# Sheet1.net
KiCad netlist of a schematic drawn in Altium Designer
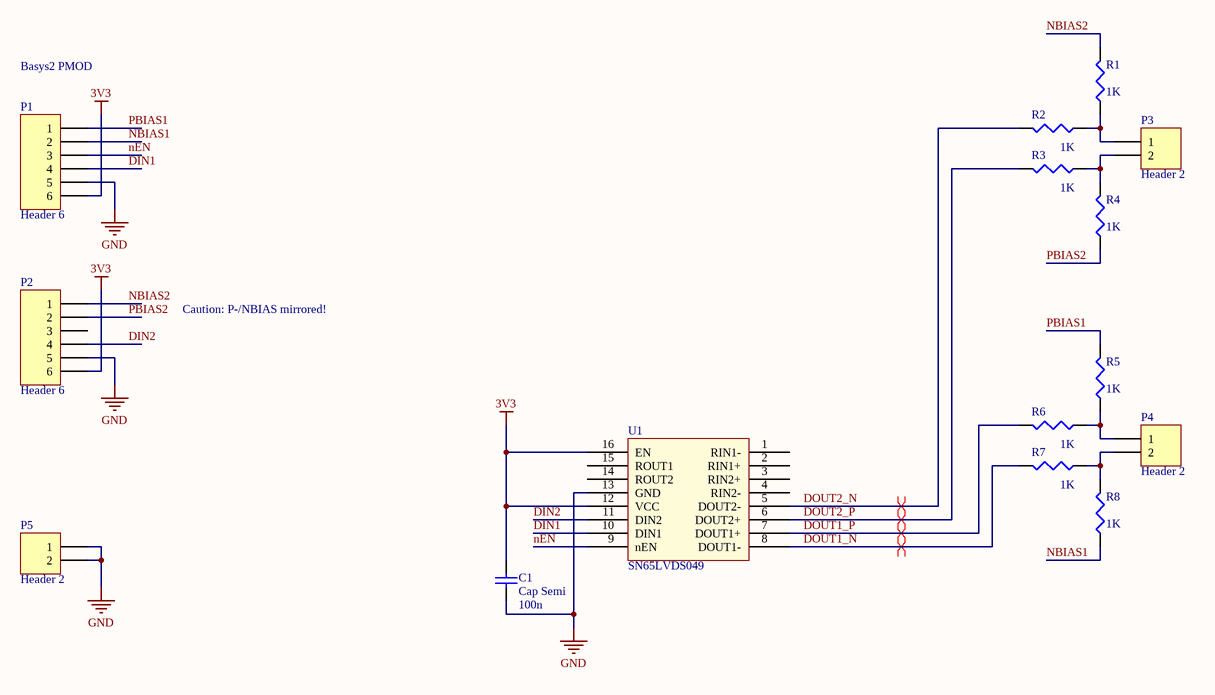
[diagram p0: Sheet1.SchDoc]

(export (version "E")
  (design (tool "Eeschema 10.0.6"))
  (components
    (comp (ref "C1")
      (value "Cap Semi")
      (footprint "1608[0603]")
      (description "Capacitor (Semiconductor SIM Model)")
      (fields (field (name "ALTIUM_VALUE") "100n") (field (name "PUBLISHER") "Altium Limited"))
      (libsource (lib "Miscellaneous Devices") (part "Cap Semi"))
    )
    (comp (ref "P1")
      (value "Header 6")
      (footprint "HDR1X6")
      (description "Header, 6-Pin")
      (fields (field (name "PUBLISHER") "Altium Limited"))
      (libsource (lib "Miscellaneous Connectors") (part "Header 6"))
    )
    (comp (ref "P2")
      (value "Header 6")
      (footprint "HDR1X6")
      (description "Header, 6-Pin")
      (fields (field (name "PUBLISHER") "Altium Limited"))
      (libsource (lib "Miscellaneous Connectors") (part "Header 6"))
    )
    (comp (ref "P3")
      (value "Header 2")
      (footprint "HDR1X2")
      (description "Header, 2-Pin")
      (fields (field (name "PUBLISHER") "Altium Limited"))
      (libsource (lib "Miscellaneous Connectors") (part "Header 2"))
    )
    (comp (ref "P4")
      (value "Header 2")
      (footprint "HDR1X2")
      (description "Header, 2-Pin")
      (fields (field (name "PUBLISHER") "Altium Limited"))
      (libsource (lib "Miscellaneous Connectors") (part "Header 2"))
    )
    (comp (ref "P5")
      (value "Header 2")
      (footprint "HDR1X2")
      (description "Header, 2-Pin")
      (fields (field (name "PUBLISHER") "Altium Limited"))
      (libsource (lib "") (part "Header 2_1"))
    )
    (comp (ref "R1")
      (value "1K")
      (footprint "J1-0603")
      (description "Resistor")
      (fields (field (name "Comment") "Res3") (field (name "PUBLISHER") "Altium Limited"))
      (libsource (lib "Miscellaneous Devices") (part "Res3"))
    )
    (comp (ref "R2")
      (value "1K")
      (footprint "J1-0603")
      (description "Resistor")
      (fields (field (name "Comment") "Res3") (field (name "PUBLISHER") "Altium Limited"))
      (libsource (lib "Miscellaneous Devices") (part "Res3"))
    )
    (comp (ref "R3")
      (value "1K")
      (footprint "J1-0603")
      (description "Resistor")
      (fields (field (name "Comment") "Res3") (field (name "PUBLISHER") "Altium Limited"))
      (libsource (lib "Miscellaneous Devices") (part "Res3"))
    )
    (comp (ref "R4")
      (value "1K")
      (footprint "J1-0603")
      (description "Resistor")
      (fields (field (name "Comment") "Res3") (field (name "PUBLISHER") "Altium Limited"))
      (libsource (lib "Miscellaneous Devices") (part "Res3"))
    )
    (comp (ref "R5")
      (value "1K")
      (footprint "J1-0603")
      (description "Resistor")
      (fields (field (name "Comment") "Res3") (field (name "PUBLISHER") "Altium Limited"))
      (libsource (lib "Miscellaneous Devices") (part "Res3"))
    )
    (comp (ref "R6")
      (value "1K")
      (footprint "J1-0603")
      (description "Resistor")
      (fields (field (name "Comment") "Res3") (field (name "PUBLISHER") "Altium Limited"))
      (libsource (lib "Miscellaneous Devices") (part "Res3"))
    )
    (comp (ref "R7")
      (value "1K")
      (footprint "J1-0603")
      (description "Resistor")
      (fields (field (name "Comment") "Res3") (field (name "PUBLISHER") "Altium Limited"))
      (libsource (lib "Miscellaneous Devices") (part "Res3"))
    )
    (comp (ref "R8")
      (value "1K")
      (footprint "J1-0603")
      (description "Resistor")
      (fields (field (name "Comment") "Res3") (field (name "PUBLISHER") "Altium Limited"))
      (libsource (lib "Miscellaneous Devices") (part "Res3"))
    )
    (comp (ref "U1")
      (value "SN65LVDS049")
      (footprint "SOP127P600-8N")
      (libsource (lib "Schlib1") (part "SN65LVDS049"))
    )
  )
  (nets
    (net (code "1") (name "/DIN1") (class "Default")
      (node (ref "P1") (pin "4") (pinfunction "4_4") (pintype "passive"))
      (node (ref "U1") (pin "10") (pinfunction "DIN1_10") (pintype "passive"))
    )
    (net (code "2") (name "/DIN2") (class "Default")
      (node (ref "P2") (pin "4") (pinfunction "4_4") (pintype "passive"))
      (node (ref "U1") (pin "11") (pinfunction "DIN2_11") (pintype "passive"))
    )
    (net (code "3") (name "/DOUT1_N") (class "Default")
      (node (ref "R7") (pin "2") (pinfunction "2_2") (pintype "passive"))
      (node (ref "U1") (pin "8") (pinfunction "DOUT1-_8") (pintype "passive"))
    )
    (net (code "4") (name "/DOUT1_P") (class "Default")
      (node (ref "R6") (pin "2") (pinfunction "2_2") (pintype "passive"))
      (node (ref "U1") (pin "7") (pinfunction "DOUT1+_7") (pintype "passive"))
    )
    (net (code "5") (name "/DOUT2_N") (class "Default")
      (node (ref "R2") (pin "2") (pinfunction "2_2") (pintype "passive"))
      (node (ref "U1") (pin "5") (pinfunction "DOUT2-_5") (pintype "passive"))
    )
    (net (code "6") (name "/DOUT2_P") (class "Default")
      (node (ref "R3") (pin "2") (pinfunction "2_2") (pintype "passive"))
      (node (ref "U1") (pin "6") (pinfunction "DOUT2+_6") (pintype "passive"))
    )
    (net (code "7") (name "/NBIAS1") (class "Default")
      (node (ref "P1") (pin "2") (pinfunction "2_2") (pintype "passive"))
      (node (ref "R8") (pin "1") (pinfunction "1_1") (pintype "passive"))
    )
    (net (code "8") (name "/NBIAS2") (class "Default")
      (node (ref "P2") (pin "1") (pinfunction "1_1") (pintype "passive"))
      (node (ref "R1") (pin "2") (pinfunction "2_2") (pintype "passive"))
    )
    (net (code "9") (name "/PBIAS1") (class "Default")
      (node (ref "P1") (pin "1") (pinfunction "1_1") (pintype "passive"))
      (node (ref "R5") (pin "2") (pinfunction "2_2") (pintype "passive"))
    )
    (net (code "10") (name "/PBIAS2") (class "Default")
      (node (ref "P2") (pin "2") (pinfunction "2_2") (pintype "passive"))
      (node (ref "R4") (pin "1") (pinfunction "1_1") (pintype "passive"))
    )
    (net (code "11") (name "/nEN") (class "Default")
      (node (ref "P1") (pin "3") (pinfunction "3_3") (pintype "passive"))
      (node (ref "U1") (pin "9") (pinfunction "nEN_9") (pintype "passive"))
    )
    (net (code "12") (name "3V3") (class "Default")
      (node (ref "C1") (pin "2") (pinfunction "2_2") (pintype "passive"))
      (node (ref "P1") (pin "6") (pinfunction "6_6") (pintype "passive"))
      (node (ref "P2") (pin "6") (pinfunction "6_6") (pintype "passive"))
      (node (ref "U1") (pin "12") (pinfunction "VCC_12") (pintype "passive"))
      (node (ref "U1") (pin "16") (pinfunction "EN_16") (pintype "passive"))
    )
    (net (code "13") (name "GND") (class "Default")
      (node (ref "C1") (pin "1") (pinfunction "1_1") (pintype "passive"))
      (node (ref "P1") (pin "5") (pinfunction "5_5") (pintype "passive"))
      (node (ref "P2") (pin "5") (pinfunction "5_5") (pintype "passive"))
      (node (ref "P5") (pin "1") (pinfunction "1_1") (pintype "passive"))
      (node (ref "P5") (pin "2") (pinfunction "2_2") (pintype "passive"))
      (node (ref "U1") (pin "13") (pinfunction "GND_13") (pintype "passive"))
    )
    (net (code "14") (name "Net-(P3-Pad1)") (class "Default")
      (node (ref "P3") (pin "1") (pinfunction "1_1") (pintype "passive"))
      (node (ref "R1") (pin "1") (pinfunction "1_1") (pintype "passive"))
      (node (ref "R2") (pin "1") (pinfunction "1_1") (pintype "passive"))
    )
    (net (code "15") (name "Net-(P3-Pad2)") (class "Default")
      (node (ref "P3") (pin "2") (pinfunction "2_2") (pintype "passive"))
      (node (ref "R3") (pin "1") (pinfunction "1_1") (pintype "passive"))
      (node (ref "R4") (pin "2") (pinfunction "2_2") (pintype "passive"))
    )
    (net (code "16") (name "Net-(P4-Pad1)") (class "Default")
      (node (ref "P4") (pin "1") (pinfunction "1_1") (pintype "passive"))
      (node (ref "R5") (pin "1") (pinfunction "1_1") (pintype "passive"))
      (node (ref "R6") (pin "1") (pinfunction "1_1") (pintype "passive"))
    )
    (net (code "17") (name "Net-(P4-Pad2)") (class "Default")
      (node (ref "P4") (pin "2") (pinfunction "2_2") (pintype "passive"))
      (node (ref "R7") (pin "1") (pinfunction "1_1") (pintype "passive"))
      (node (ref "R8") (pin "2") (pinfunction "2_2") (pintype "passive"))
    )
    (net (code "18") (name "unconnected-(P2-Pad3)") (class "Default")
      (node (ref "P2") (pin "3") (pinfunction "3_3") (pintype "passive"))
    )
    (net (code "19") (name "unconnected-(U1-RIN1+-Pad2)") (class "Default")
      (node (ref "U1") (pin "2") (pinfunction "RIN1+_2") (pintype "passive"))
    )
    (net (code "20") (name "unconnected-(U1-RIN1--Pad1)") (class "Default")
      (node (ref "U1") (pin "1") (pinfunction "RIN1-_1") (pintype "passive"))
    )
    (net (code "21") (name "unconnected-(U1-RIN2+-Pad3)") (class "Default")
      (node (ref "U1") (pin "3") (pinfunction "RIN2+_3") (pintype "passive"))
    )
    (net (code "22") (name "unconnected-(U1-RIN2--Pad4)") (class "Default")
      (node (ref "U1") (pin "4") (pinfunction "RIN2-_4") (pintype "passive"))
    )
    (net (code "23") (name "unconnected-(U1-ROUT1-Pad15)") (class "Default")
      (node (ref "U1") (pin "15") (pinfunction "ROUT1_15") (pintype "passive"))
    )
    (net (code "24") (name "unconnected-(U1-ROUT2-Pad14)") (class "Default")
      (node (ref "U1") (pin "14") (pinfunction "ROUT2_14") (pintype "passive"))
    )
  )
)
